# Mainboard_v2.net
KiCad netlist of a schematic drawn in EAGLE
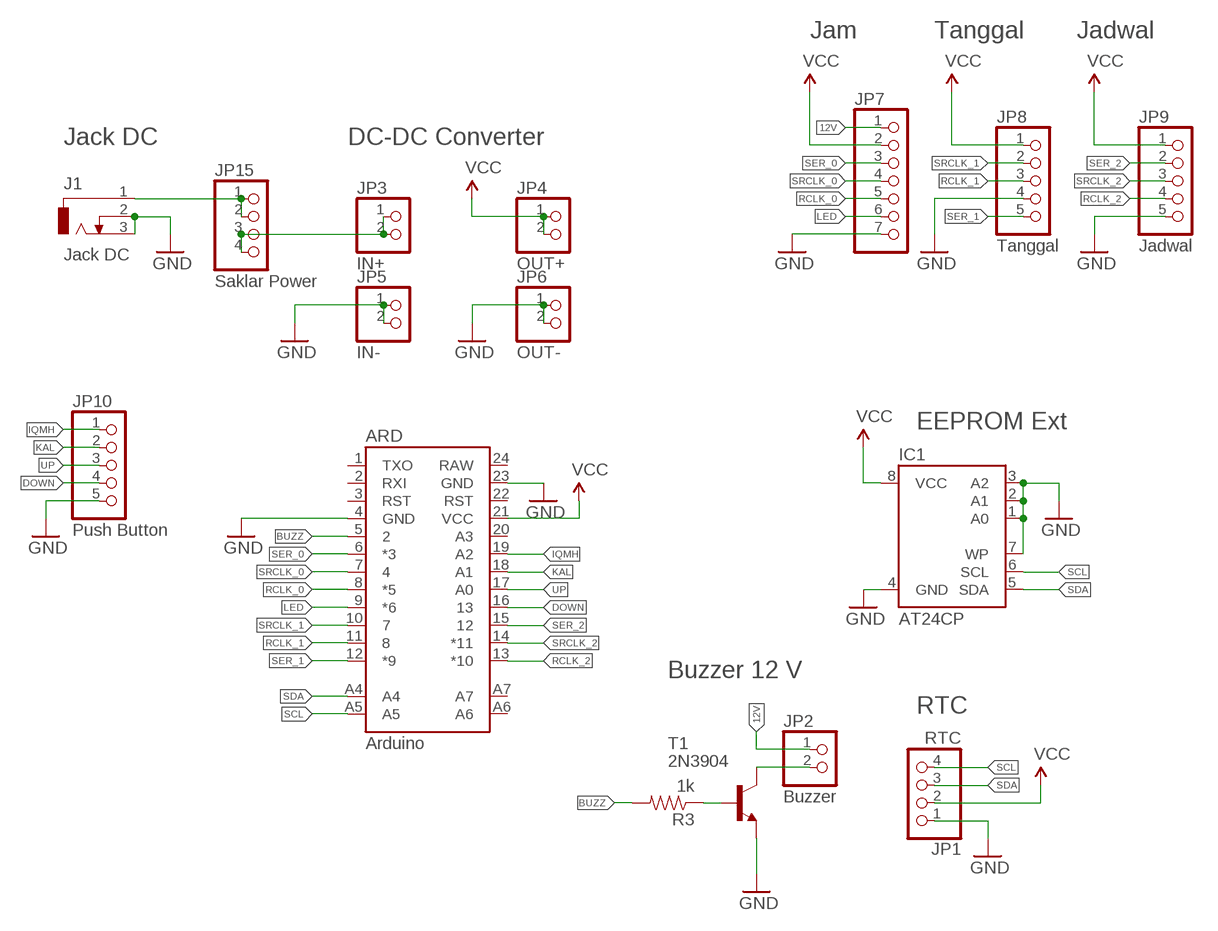
[diagram p0: schematic, sheet 1]

(export (version "E")
  (design (tool "Eeschema 10.0.6"))
  (components
    (comp (ref "ARD")
      (value "Arduino")
      (footprint "eagle-import:ARDUINO_PRO_MINI")
      (libsource (lib "eagle-import") (part "ARDUINO_PRO_MINIARDUINO_PRO_MINI_MODIFIED"))
    )
    (comp (ref "IC1")
      (value "AT24CP")
      (footprint "eagle-import:DIL08")
      (fields (field (name "MPN") "AT24C1024BW-SH-B"))
      (libsource (lib "eagle-import") (part "AT24CP"))
    )
    (comp (ref "J1")
      (value "Jack DC")
      (footprint "eagle-import:DCJ0202")
      (libsource (lib "eagle-import") (part "DCJ0202"))
    )
    (comp (ref "JP1")
      (value "RTC")
      (footprint "eagle-import:1X04")
      (libsource (lib "eagle-import") (part "PINHD-1X4"))
    )
    (comp (ref "JP2")
      (value "Buzzer")
      (footprint "eagle-import:1X02")
      (libsource (lib "eagle-import") (part "PINHD-1X2"))
    )
    (comp (ref "JP3")
      (value "IN+")
      (footprint "eagle-import:1X02")
      (libsource (lib "eagle-import") (part "PINHD-1X2"))
    )
    (comp (ref "JP4")
      (value "OUT+")
      (footprint "eagle-import:1X02")
      (libsource (lib "eagle-import") (part "PINHD-1X2"))
    )
    (comp (ref "JP5")
      (value "IN-")
      (footprint "eagle-import:1X02")
      (libsource (lib "eagle-import") (part "PINHD-1X2"))
    )
    (comp (ref "JP6")
      (value "OUT-")
      (footprint "eagle-import:1X02")
      (libsource (lib "eagle-import") (part "PINHD-1X2"))
    )
    (comp (ref "JP7")
      (value "PINHD-1X7")
      (footprint "eagle-import:1X07")
      (libsource (lib "eagle-import") (part "PINHD-1X7"))
    )
    (comp (ref "JP8")
      (value "Tanggal")
      (footprint "eagle-import:1X05")
      (libsource (lib "eagle-import") (part "PINHD-1X5"))
    )
    (comp (ref "JP9")
      (value "Jadwal")
      (footprint "eagle-import:1X05")
      (libsource (lib "eagle-import") (part "PINHD-1X5"))
    )
    (comp (ref "JP10")
      (value "Push Button")
      (footprint "eagle-import:1X05")
      (libsource (lib "eagle-import") (part "PINHD-1X5"))
    )
    (comp (ref "JP15")
      (value "Saklar Power")
      (footprint "eagle-import:1X04")
      (libsource (lib "eagle-import") (part "PINHD-1X4"))
    )
    (comp (ref "R3")
      (value "1k")
      (footprint "eagle-import:AXIAL-0.4")
      (libsource (lib "eagle-import") (part "RESISTORPTH-1/4W"))
    )
    (comp (ref "T1")
      (value "2N3904")
      (footprint "eagle-import:TO92")
      (libsource (lib "eagle-import") (part "2N3904"))
    )
  )
  (nets
    (net (code "1") (name "12V") (class "Default")
      (node (ref "JP15") (pin "3") (pinfunction "3_3") (pintype "passive"))
      (node (ref "JP15") (pin "4") (pinfunction "4_4") (pintype "passive"))
      (node (ref "JP2") (pin "1") (pinfunction "1_1") (pintype "passive"))
      (node (ref "JP3") (pin "1") (pinfunction "1_1") (pintype "passive"))
      (node (ref "JP3") (pin "2") (pinfunction "2_2") (pintype "passive"))
      (node (ref "JP7") (pin "1") (pinfunction "1_1") (pintype "passive"))
    )
    (net (code "2") (name "BUZZ") (class "Default")
      (node (ref "ARD") (pin "5") (pinfunction "2_5") (pintype "bidirectional"))
      (node (ref "R3") (pin "P$2") (pinfunction "2_P$2") (pintype "passive"))
    )
    (net (code "3") (name "DOWN") (class "Default")
      (node (ref "ARD") (pin "16") (pinfunction "13_16") (pintype "bidirectional"))
      (node (ref "JP10") (pin "4") (pinfunction "4_4") (pintype "passive"))
    )
    (net (code "4") (name "GND") (class "Default")
      (node (ref "ARD") (pin "23") (pinfunction "GND_23") (pintype "bidirectional"))
      (node (ref "ARD") (pin "4") (pinfunction "GND_4") (pintype "bidirectional"))
      (node (ref "IC1") (pin "1") (pinfunction "A0_1") (pintype "input"))
      (node (ref "IC1") (pin "2") (pinfunction "A1_2") (pintype "input"))
      (node (ref "IC1") (pin "3") (pinfunction "A2_3") (pintype "input"))
      (node (ref "IC1") (pin "4") (pinfunction "GND_4") (pintype "power_in"))
      (node (ref "IC1") (pin "7") (pinfunction "WP_7") (pintype "input"))
      (node (ref "J1") (pin "2") (pinfunction "2_2") (pintype "passive"))
      (node (ref "J1") (pin "3") (pinfunction "3_3") (pintype "passive"))
      (node (ref "JP1") (pin "1") (pinfunction "1_1") (pintype "passive"))
      (node (ref "JP10") (pin "5") (pinfunction "5_5") (pintype "passive"))
      (node (ref "JP5") (pin "1") (pinfunction "1_1") (pintype "passive"))
      (node (ref "JP5") (pin "2") (pinfunction "2_2") (pintype "passive"))
      (node (ref "JP6") (pin "1") (pinfunction "1_1") (pintype "passive"))
      (node (ref "JP6") (pin "2") (pinfunction "2_2") (pintype "passive"))
      (node (ref "JP7") (pin "7") (pinfunction "7_7") (pintype "passive"))
      (node (ref "JP8") (pin "4") (pinfunction "4_4") (pintype "passive"))
      (node (ref "JP9") (pin "5") (pinfunction "5_5") (pintype "passive"))
      (node (ref "T1") (pin "3") (pinfunction "E_3") (pintype "passive"))
    )
    (net (code "5") (name "IQMH") (class "Default")
      (node (ref "ARD") (pin "19") (pinfunction "A2_19") (pintype "bidirectional"))
      (node (ref "JP10") (pin "1") (pinfunction "1_1") (pintype "passive"))
    )
    (net (code "6") (name "KAL") (class "Default")
      (node (ref "ARD") (pin "18") (pinfunction "A1_18") (pintype "bidirectional"))
      (node (ref "JP10") (pin "2") (pinfunction "2_2") (pintype "passive"))
    )
    (net (code "7") (name "LED") (class "Default")
      (node (ref "ARD") (pin "9") (pinfunction "*6_9") (pintype "bidirectional"))
      (node (ref "JP7") (pin "6") (pinfunction "6_6") (pintype "passive"))
    )
    (net (code "8") (name "Net-(J1-Pad1)") (class "Default")
      (node (ref "J1") (pin "1") (pinfunction "1_1") (pintype "passive"))
      (node (ref "JP15") (pin "1") (pinfunction "1_1") (pintype "passive"))
      (node (ref "JP15") (pin "2") (pinfunction "2_2") (pintype "passive"))
    )
    (net (code "9") (name "Net-(R3-1)") (class "Default")
      (node (ref "R3") (pin "P$1") (pinfunction "1_P$1") (pintype "passive"))
      (node (ref "T1") (pin "2") (pinfunction "B_2") (pintype "passive"))
    )
    (net (code "10") (name "Net-(T1-C)") (class "Default")
      (node (ref "JP2") (pin "2") (pinfunction "2_2") (pintype "passive"))
      (node (ref "T1") (pin "1") (pinfunction "C_1") (pintype "passive"))
    )
    (net (code "11") (name "RCLK_0") (class "Default")
      (node (ref "ARD") (pin "8") (pinfunction "*5_8") (pintype "bidirectional"))
      (node (ref "JP7") (pin "5") (pinfunction "5_5") (pintype "passive"))
    )
    (net (code "12") (name "RCLK_1") (class "Default")
      (node (ref "ARD") (pin "11") (pinfunction "8_11") (pintype "bidirectional"))
      (node (ref "JP8") (pin "3") (pinfunction "3_3") (pintype "passive"))
    )
    (net (code "13") (name "RCLK_2") (class "Default")
      (node (ref "ARD") (pin "13") (pinfunction "*10_13") (pintype "bidirectional"))
      (node (ref "JP9") (pin "4") (pinfunction "4_4") (pintype "passive"))
    )
    (net (code "14") (name "SCL") (class "Default")
      (node (ref "ARD") (pin "A5") (pinfunction "A5_A5") (pintype "bidirectional"))
      (node (ref "IC1") (pin "6") (pinfunction "SCL_6") (pintype "bidirectional"))
      (node (ref "JP1") (pin "4") (pinfunction "4_4") (pintype "passive"))
    )
    (net (code "15") (name "SDA") (class "Default")
      (node (ref "ARD") (pin "A4") (pinfunction "A4_A4") (pintype "bidirectional"))
      (node (ref "IC1") (pin "5") (pinfunction "SDA_5") (pintype "bidirectional"))
      (node (ref "JP1") (pin "3") (pinfunction "3_3") (pintype "passive"))
    )
    (net (code "16") (name "SER_0") (class "Default")
      (node (ref "ARD") (pin "6") (pinfunction "*3_6") (pintype "bidirectional"))
      (node (ref "JP7") (pin "3") (pinfunction "3_3") (pintype "passive"))
    )
    (net (code "17") (name "SER_1") (class "Default")
      (node (ref "ARD") (pin "12") (pinfunction "*9_12") (pintype "bidirectional"))
      (node (ref "JP8") (pin "5") (pinfunction "5_5") (pintype "passive"))
    )
    (net (code "18") (name "SER_2") (class "Default")
      (node (ref "ARD") (pin "15") (pinfunction "12_15") (pintype "bidirectional"))
      (node (ref "JP9") (pin "2") (pinfunction "2_2") (pintype "passive"))
    )
    (net (code "19") (name "SRCLK_0") (class "Default")
      (node (ref "ARD") (pin "7") (pinfunction "4_7") (pintype "bidirectional"))
      (node (ref "JP7") (pin "4") (pinfunction "4_4") (pintype "passive"))
    )
    (net (code "20") (name "SRCLK_1") (class "Default")
      (node (ref "ARD") (pin "10") (pinfunction "7_10") (pintype "bidirectional"))
      (node (ref "JP8") (pin "2") (pinfunction "2_2") (pintype "passive"))
    )
    (net (code "21") (name "SRCLK_2") (class "Default")
      (node (ref "ARD") (pin "14") (pinfunction "*11_14") (pintype "bidirectional"))
      (node (ref "JP9") (pin "3") (pinfunction "3_3") (pintype "passive"))
    )
    (net (code "22") (name "UP") (class "Default")
      (node (ref "ARD") (pin "17") (pinfunction "A0_17") (pintype "bidirectional"))
      (node (ref "JP10") (pin "3") (pinfunction "3_3") (pintype "passive"))
    )
    (net (code "23") (name "VCC") (class "Default")
      (node (ref "ARD") (pin "21") (pinfunction "VCC_21") (pintype "bidirectional"))
      (node (ref "IC1") (pin "8") (pinfunction "VCC_8") (pintype "power_in"))
      (node (ref "JP1") (pin "2") (pinfunction "2_2") (pintype "passive"))
      (node (ref "JP4") (pin "1") (pinfunction "1_1") (pintype "passive"))
      (node (ref "JP4") (pin "2") (pinfunction "2_2") (pintype "passive"))
      (node (ref "JP7") (pin "2") (pinfunction "2_2") (pintype "passive"))
      (node (ref "JP8") (pin "1") (pinfunction "1_1") (pintype "passive"))
      (node (ref "JP9") (pin "1") (pinfunction "1_1") (pintype "passive"))
    )
    (net (code "24") (name "unconnected-(ARD-A3-Pad20)") (class "Default")
      (node (ref "ARD") (pin "20") (pinfunction "A3_20") (pintype "bidirectional"))
    )
    (net (code "25") (name "unconnected-(ARD-PadA6)") (class "Default")
      (node (ref "ARD") (pin "A6") (pinfunction "A6_A6") (pintype "bidirectional"))
    )
    (net (code "26") (name "unconnected-(ARD-PadA7)") (class "Default")
      (node (ref "ARD") (pin "A7") (pinfunction "A7_A7") (pintype "bidirectional"))
    )
    (net (code "27") (name "unconnected-(ARD-RAW-Pad24)") (class "Default")
      (node (ref "ARD") (pin "24") (pinfunction "RAW_24") (pintype "bidirectional"))
    )
    (net (code "28") (name "unconnected-(ARD-RST-Pad3)") (class "Default")
      (node (ref "ARD") (pin "3") (pinfunction "RST_3") (pintype "bidirectional"))
    )
    (net (code "29") (name "unconnected-(ARD-RST-Pad22)") (class "Default")
      (node (ref "ARD") (pin "22") (pinfunction "RST_22") (pintype "bidirectional"))
    )
    (net (code "30") (name "unconnected-(ARD-RXI-Pad2)") (class "Default")
      (node (ref "ARD") (pin "2") (pinfunction "RXI_2") (pintype "bidirectional"))
    )
    (net (code "31") (name "unconnected-(ARD-TXO-Pad1)") (class "Default")
      (node (ref "ARD") (pin "1") (pinfunction "TXO_1") (pintype "bidirectional"))
    )
  )
)
